# smartsensor.net
KiCad netlist of a schematic drawn in EAGLE
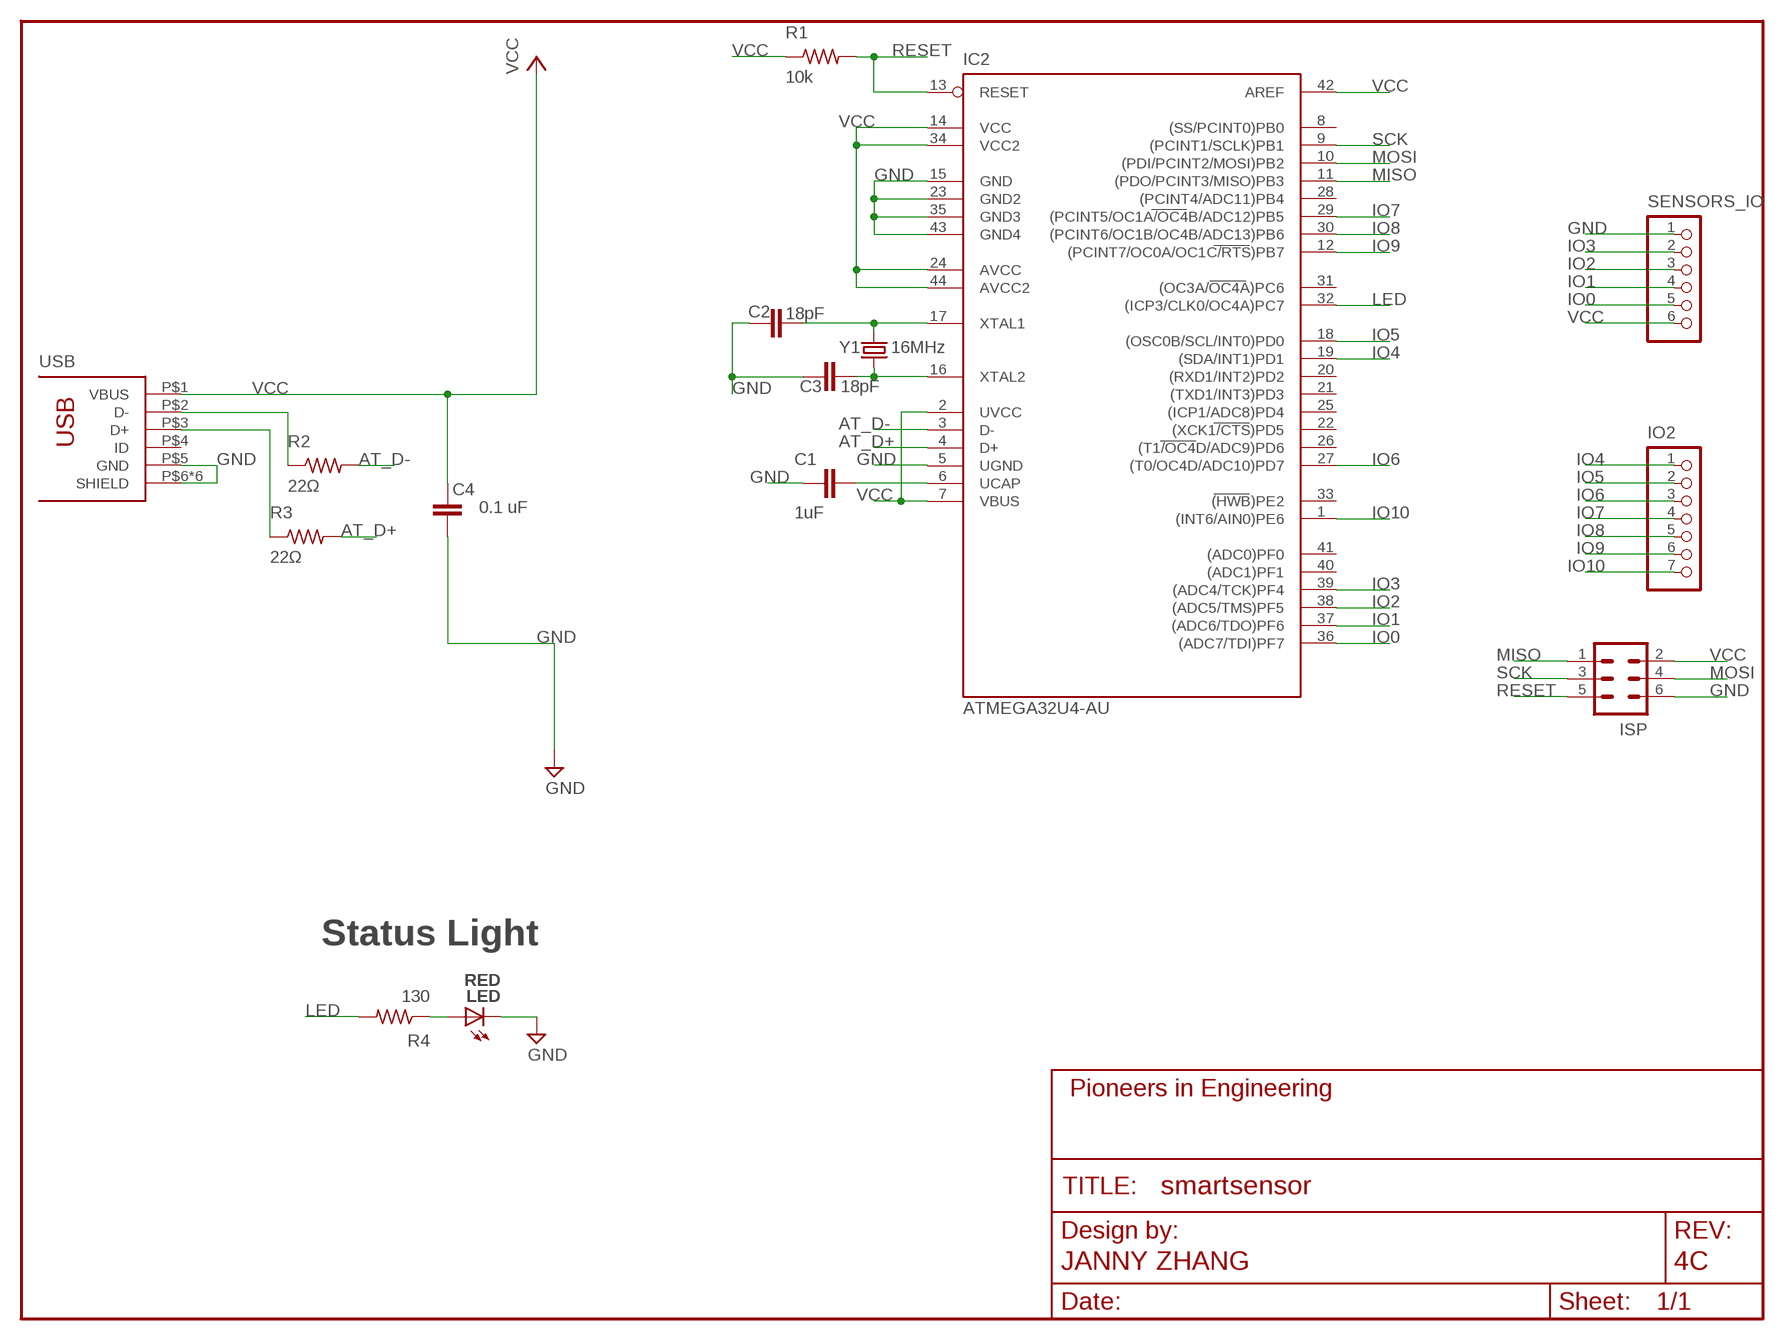
[diagram p0: schematic, sheet 1]

(export (version "E")
  (design (tool "Eeschema 10.0.6"))
  (components
    (comp (ref "C1")
      (value "1uF")
      (footprint "eagle-import:0603-CAP")
      (libsource (lib "eagle-import") (part "CAP0603-CAP"))
    )
    (comp (ref "C2")
      (value "18pF")
      (footprint "eagle-import:0603-CAP")
      (libsource (lib "eagle-import") (part "CAP0603-CAP"))
    )
    (comp (ref "C3")
      (value "18pF")
      (footprint "eagle-import:0603-CAP")
      (libsource (lib "eagle-import") (part "CAP0603-CAP"))
    )
    (comp (ref "C4")
      (value "0.1 uF")
      (footprint "eagle-import:0603-CAP")
      (libsource (lib "eagle-import") (part "CAP0603-CAP"))
    )
    (comp (ref "IC2")
      (value "ATMEGA32U4-AU")
      (footprint "eagle-import:TQFP44")
      (libsource (lib "eagle-import") (part "ATMEGA32U4-AU"))
    )
    (comp (ref "IO2")
      (value "PINHD-1X7")
      (footprint "eagle-import:1X07")
      (libsource (lib "eagle-import") (part "PINHD-1X7"))
    )
    (comp (ref "ISP")
      (value "MA03-2")
      (footprint "eagle-import:MA03-2")
      (libsource (lib "eagle-import") (part "MA03-2"))
    )
    (comp (ref "LED")
      (value "RED")
      (footprint "eagle-import:LED-0805")
      (libsource (lib "eagle-import") (part "LED0805"))
    )
    (comp (ref "R1")
      (value "10k")
      (footprint "eagle-import:R0603")
      (libsource (lib "eagle-import") (part "R-US_R0603"))
    )
    (comp (ref "R2")
      (value "22Ω")
      (footprint "eagle-import:R0603")
      (libsource (lib "eagle-import") (part "R-US_R0603"))
    )
    (comp (ref "R3")
      (value "22Ω")
      (footprint "eagle-import:R0603")
      (libsource (lib "eagle-import") (part "R-US_R0603"))
    )
    (comp (ref "R4")
      (value "130")
      (footprint "eagle-import:R0603")
      (libsource (lib "eagle-import") (part "R-US_R0603"))
    )
    (comp (ref "SENSORS_IO")
      (value "PINHD-1X6STRAIN-RELIEF")
      (footprint "eagle-import:1X06-STRAINRELIEF")
      (libsource (lib "eagle-import") (part "PINHD-1X6STRAIN-RELIEF"))
    )
    (comp (ref "USB")
      (value "USB-OTGMICRO-AB")
      (footprint "eagle-import:USB-MICRO-AB")
      (libsource (lib "eagle-import") (part "USB-OTGMICRO-AB"))
    )
    (comp (ref "Y1")
      (value "16MHz")
      (footprint "eagle-import:CRYSTAL-SMD-5.0X3.2-2PIN")
      (libsource (lib "eagle-import") (part "CRYSTAL5.0X3.2"))
    )
  )
  (nets
    (net (code "1") (name "/AT_D+") (class "Default")
      (node (ref "IC2") (pin "4") (pinfunction "D+_4") (pintype "bidirectional"))
      (node (ref "R3") (pin "2") (pinfunction "2_2") (pintype "passive"))
    )
    (net (code "2") (name "/AT_D-") (class "Default")
      (node (ref "IC2") (pin "3") (pinfunction "D-_3") (pintype "bidirectional"))
      (node (ref "R2") (pin "2") (pinfunction "2_2") (pintype "passive"))
    )
    (net (code "3") (name "/IO0") (class "Default")
      (node (ref "IC2") (pin "36") (pinfunction "(ADC7/TDI)PF7_36") (pintype "bidirectional"))
      (node (ref "SENSORS_IO") (pin "5") (pinfunction "5_5") (pintype "passive"))
    )
    (net (code "4") (name "/IO1") (class "Default")
      (node (ref "IC2") (pin "37") (pinfunction "(ADC6/TDO)PF6_37") (pintype "bidirectional"))
      (node (ref "SENSORS_IO") (pin "4") (pinfunction "4_4") (pintype "passive"))
    )
    (net (code "5") (name "/IO2") (class "Default")
      (node (ref "IC2") (pin "38") (pinfunction "(ADC5/TMS)PF5_38") (pintype "bidirectional"))
      (node (ref "SENSORS_IO") (pin "3") (pinfunction "3_3") (pintype "passive"))
    )
    (net (code "6") (name "/IO3") (class "Default")
      (node (ref "IC2") (pin "39") (pinfunction "(ADC4/TCK)PF4_39") (pintype "bidirectional"))
      (node (ref "SENSORS_IO") (pin "2") (pinfunction "2_2") (pintype "passive"))
    )
    (net (code "7") (name "/IO4") (class "Default")
      (node (ref "IC2") (pin "19") (pinfunction "(SDA/INT1)PD1_19") (pintype "bidirectional"))
      (node (ref "IO2") (pin "1") (pinfunction "1_1") (pintype "passive"))
    )
    (net (code "8") (name "/IO5") (class "Default")
      (node (ref "IC2") (pin "18") (pinfunction "(OSC0B/SCL/INT0)PD0_18") (pintype "bidirectional"))
      (node (ref "IO2") (pin "2") (pinfunction "2_2") (pintype "passive"))
    )
    (net (code "9") (name "/IO6") (class "Default")
      (node (ref "IC2") (pin "27") (pinfunction "(T0/OC4D/ADC10)PD7_27") (pintype "bidirectional"))
      (node (ref "IO2") (pin "3") (pinfunction "3_3") (pintype "passive"))
    )
    (net (code "10") (name "/IO7") (class "Default")
      (node (ref "IC2") (pin "29") (pinfunction "(PCINT5/OC1A/OC4B/ADC12)PB5_29") (pintype "bidirectional"))
      (node (ref "IO2") (pin "4") (pinfunction "4_4") (pintype "passive"))
    )
    (net (code "11") (name "/IO8") (class "Default")
      (node (ref "IC2") (pin "30") (pinfunction "(PCINT6/OC1B/OC4B/ADC13)PB6_30") (pintype "bidirectional"))
      (node (ref "IO2") (pin "5") (pinfunction "5_5") (pintype "passive"))
    )
    (net (code "12") (name "/IO9") (class "Default")
      (node (ref "IC2") (pin "12") (pinfunction "(PCINT7/OC0A/OC1C/RTS)PB7_12") (pintype "bidirectional"))
      (node (ref "IO2") (pin "6") (pinfunction "6_6") (pintype "passive"))
    )
    (net (code "13") (name "/IO10") (class "Default")
      (node (ref "IC2") (pin "1") (pinfunction "(INT6/AIN0)PE6_1") (pintype "bidirectional"))
      (node (ref "IO2") (pin "7") (pinfunction "7_7") (pintype "passive"))
    )
    (net (code "14") (name "/LED") (class "Default")
      (node (ref "IC2") (pin "32") (pinfunction "(ICP3/CLK0/OC4A)PC7_32") (pintype "bidirectional"))
      (node (ref "R4") (pin "2") (pinfunction "2_2") (pintype "passive"))
    )
    (net (code "15") (name "/MISO") (class "Default")
      (node (ref "IC2") (pin "11") (pinfunction "(PDO/PCINT3/MISO)PB3_11") (pintype "bidirectional"))
      (node (ref "ISP") (pin "1") (pinfunction "1_1") (pintype "passive"))
    )
    (net (code "16") (name "/MOSI") (class "Default")
      (node (ref "IC2") (pin "10") (pinfunction "(PDI/PCINT2/MOSI)PB2_10") (pintype "bidirectional"))
      (node (ref "ISP") (pin "4") (pinfunction "4_4") (pintype "passive"))
    )
    (net (code "17") (name "/RESET") (class "Default")
      (node (ref "IC2") (pin "13") (pinfunction "RESET_13") (pintype "bidirectional"))
      (node (ref "ISP") (pin "5") (pinfunction "5_5") (pintype "passive"))
      (node (ref "R1") (pin "2") (pinfunction "2_2") (pintype "passive"))
    )
    (net (code "18") (name "/SCK") (class "Default")
      (node (ref "IC2") (pin "9") (pinfunction "(PCINT1/SCLK)PB1_9") (pintype "bidirectional"))
      (node (ref "ISP") (pin "3") (pinfunction "3_3") (pintype "passive"))
    )
    (net (code "19") (name "GND") (class "Default")
      (node (ref "C1") (pin "1") (pinfunction "1_1") (pintype "passive"))
      (node (ref "C2") (pin "1") (pinfunction "1_1") (pintype "passive"))
      (node (ref "C3") (pin "1") (pinfunction "1_1") (pintype "passive"))
      (node (ref "C4") (pin "1") (pinfunction "1_1") (pintype "passive"))
      (node (ref "IC2") (pin "15") (pinfunction "GND_15") (pintype "bidirectional"))
      (node (ref "IC2") (pin "23") (pinfunction "GND2_23") (pintype "bidirectional"))
      (node (ref "IC2") (pin "35") (pinfunction "GND3_35") (pintype "bidirectional"))
      (node (ref "IC2") (pin "43") (pinfunction "GND4_43") (pintype "bidirectional"))
      (node (ref "IC2") (pin "5") (pinfunction "UGND_5") (pintype "bidirectional"))
      (node (ref "ISP") (pin "6") (pinfunction "6_6") (pintype "passive"))
      (node (ref "LED") (pin "C") (pinfunction "C_C") (pintype "passive"))
      (node (ref "SENSORS_IO") (pin "1") (pinfunction "1_1") (pintype "passive"))
      (node (ref "USB") (pin "P$10") (pinfunction "SHIELD_P$10") (pintype "bidirectional"))
      (node (ref "USB") (pin "P$11") (pinfunction "SHIELD_P$11") (pintype "bidirectional"))
      (node (ref "USB") (pin "P$5") (pinfunction "GND_P$5") (pintype "bidirectional"))
      (node (ref "USB") (pin "P$6") (pinfunction "SHIELD_P$6") (pintype "bidirectional"))
      (node (ref "USB") (pin "P$7") (pinfunction "SHIELD_P$7") (pintype "bidirectional"))
      (node (ref "USB") (pin "P$8") (pinfunction "SHIELD_P$8") (pintype "bidirectional"))
      (node (ref "USB") (pin "P$9") (pinfunction "SHIELD_P$9") (pintype "bidirectional"))
    )
    (net (code "20") (name "Net-(IC2-UCAP)") (class "Default")
      (node (ref "C1") (pin "2") (pinfunction "2_2") (pintype "passive"))
      (node (ref "IC2") (pin "6") (pinfunction "UCAP_6") (pintype "bidirectional"))
    )
    (net (code "21") (name "Net-(IC2-XTAL1)") (class "Default")
      (node (ref "C2") (pin "2") (pinfunction "2_2") (pintype "passive"))
      (node (ref "IC2") (pin "17") (pinfunction "XTAL1_17") (pintype "bidirectional"))
      (node (ref "Y1") (pin "P$2") (pinfunction "2_P$2") (pintype "passive"))
    )
    (net (code "22") (name "Net-(IC2-XTAL2)") (class "Default")
      (node (ref "C3") (pin "2") (pinfunction "2_2") (pintype "passive"))
      (node (ref "IC2") (pin "16") (pinfunction "XTAL2_16") (pintype "bidirectional"))
      (node (ref "Y1") (pin "P$1") (pinfunction "1_P$1") (pintype "passive"))
    )
    (net (code "23") (name "Net-(LED-PadA)") (class "Default")
      (node (ref "LED") (pin "A") (pinfunction "A_A") (pintype "passive"))
      (node (ref "R4") (pin "1") (pinfunction "1_1") (pintype "passive"))
    )
    (net (code "24") (name "Net-(USB-D+)") (class "Default")
      (node (ref "R3") (pin "1") (pinfunction "1_1") (pintype "passive"))
      (node (ref "USB") (pin "P$3") (pinfunction "D+_P$3") (pintype "bidirectional"))
    )
    (net (code "25") (name "Net-(USB-D-)") (class "Default")
      (node (ref "R2") (pin "1") (pinfunction "1_1") (pintype "passive"))
      (node (ref "USB") (pin "P$2") (pinfunction "D-_P$2") (pintype "bidirectional"))
    )
    (net (code "26") (name "VCC") (class "Default")
      (node (ref "C4") (pin "2") (pinfunction "2_2") (pintype "passive"))
      (node (ref "IC2") (pin "14") (pinfunction "VCC_14") (pintype "bidirectional"))
      (node (ref "IC2") (pin "2") (pinfunction "UVCC_2") (pintype "bidirectional"))
      (node (ref "IC2") (pin "24") (pinfunction "AVCC_24") (pintype "bidirectional"))
      (node (ref "IC2") (pin "34") (pinfunction "VCC2_34") (pintype "bidirectional"))
      (node (ref "IC2") (pin "42") (pinfunction "AREF_42") (pintype "bidirectional"))
      (node (ref "IC2") (pin "44") (pinfunction "AVCC2_44") (pintype "bidirectional"))
      (node (ref "IC2") (pin "7") (pinfunction "VBUS_7") (pintype "bidirectional"))
      (node (ref "ISP") (pin "2") (pinfunction "2_2") (pintype "passive"))
      (node (ref "R1") (pin "1") (pinfunction "1_1") (pintype "passive"))
      (node (ref "SENSORS_IO") (pin "6") (pinfunction "6_6") (pintype "passive"))
      (node (ref "USB") (pin "P$1") (pinfunction "VBUS_P$1") (pintype "bidirectional"))
    )
    (net (code "27") (name "unconnected-(IC2-(ADC0)PF0-Pad41)") (class "Default")
      (node (ref "IC2") (pin "41") (pinfunction "(ADC0)PF0_41") (pintype "bidirectional"))
    )
    (net (code "28") (name "unconnected-(IC2-(ADC1)PF1-Pad40)") (class "Default")
      (node (ref "IC2") (pin "40") (pinfunction "(ADC1)PF1_40") (pintype "bidirectional"))
    )
    (net (code "29") (name "unconnected-(IC2-(HWB)PE2-Pad33)") (class "Default")
      (node (ref "IC2") (pin "33") (pinfunction "(HWB)PE2_33") (pintype "bidirectional"))
    )
    (net (code "30") (name "unconnected-(IC2-(ICP1{slash}ADC8)PD4-Pad25)") (class "Default")
      (node (ref "IC2") (pin "25") (pinfunction "(ICP1/ADC8)PD4_25") (pintype "bidirectional"))
    )
    (net (code "31") (name "unconnected-(IC2-(OC3A{slash}OC4A)PC6-Pad31)") (class "Default")
      (node (ref "IC2") (pin "31") (pinfunction "(OC3A/OC4A)PC6_31") (pintype "bidirectional"))
    )
    (net (code "32") (name "unconnected-(IC2-(PCINT4{slash}ADC11)PB4-Pad28)") (class "Default")
      (node (ref "IC2") (pin "28") (pinfunction "(PCINT4/ADC11)PB4_28") (pintype "bidirectional"))
    )
    (net (code "33") (name "unconnected-(IC2-(RXD1{slash}INT2)PD2-Pad20)") (class "Default")
      (node (ref "IC2") (pin "20") (pinfunction "(RXD1/INT2)PD2_20") (pintype "bidirectional"))
    )
    (net (code "34") (name "unconnected-(IC2-(SS{slash}PCINT0)PB0-Pad8)") (class "Default")
      (node (ref "IC2") (pin "8") (pinfunction "(SS/PCINT0)PB0_8") (pintype "bidirectional"))
    )
    (net (code "35") (name "unconnected-(IC2-(T1{slash}OC4D{slash}ADC9)PD6-Pad26)") (class "Default")
      (node (ref "IC2") (pin "26") (pinfunction "(T1/OC4D/ADC9)PD6_26") (pintype "bidirectional"))
    )
    (net (code "36") (name "unconnected-(IC2-(TXD1{slash}INT3)PD3-Pad21)") (class "Default")
      (node (ref "IC2") (pin "21") (pinfunction "(TXD1/INT3)PD3_21") (pintype "bidirectional"))
    )
    (net (code "37") (name "unconnected-(IC2-(XCK1{slash}CTS)PD5-Pad22)") (class "Default")
      (node (ref "IC2") (pin "22") (pinfunction "(XCK1/CTS)PD5_22") (pintype "bidirectional"))
    )
    (net (code "38") (name "unconnected-(USB-ID-PadP$4)") (class "Default")
      (node (ref "USB") (pin "P$4") (pinfunction "ID_P$4") (pintype "bidirectional"))
    )
  )
)
